# world_clock_2_0.net
KiCad netlist of a schematic drawn in EAGLE
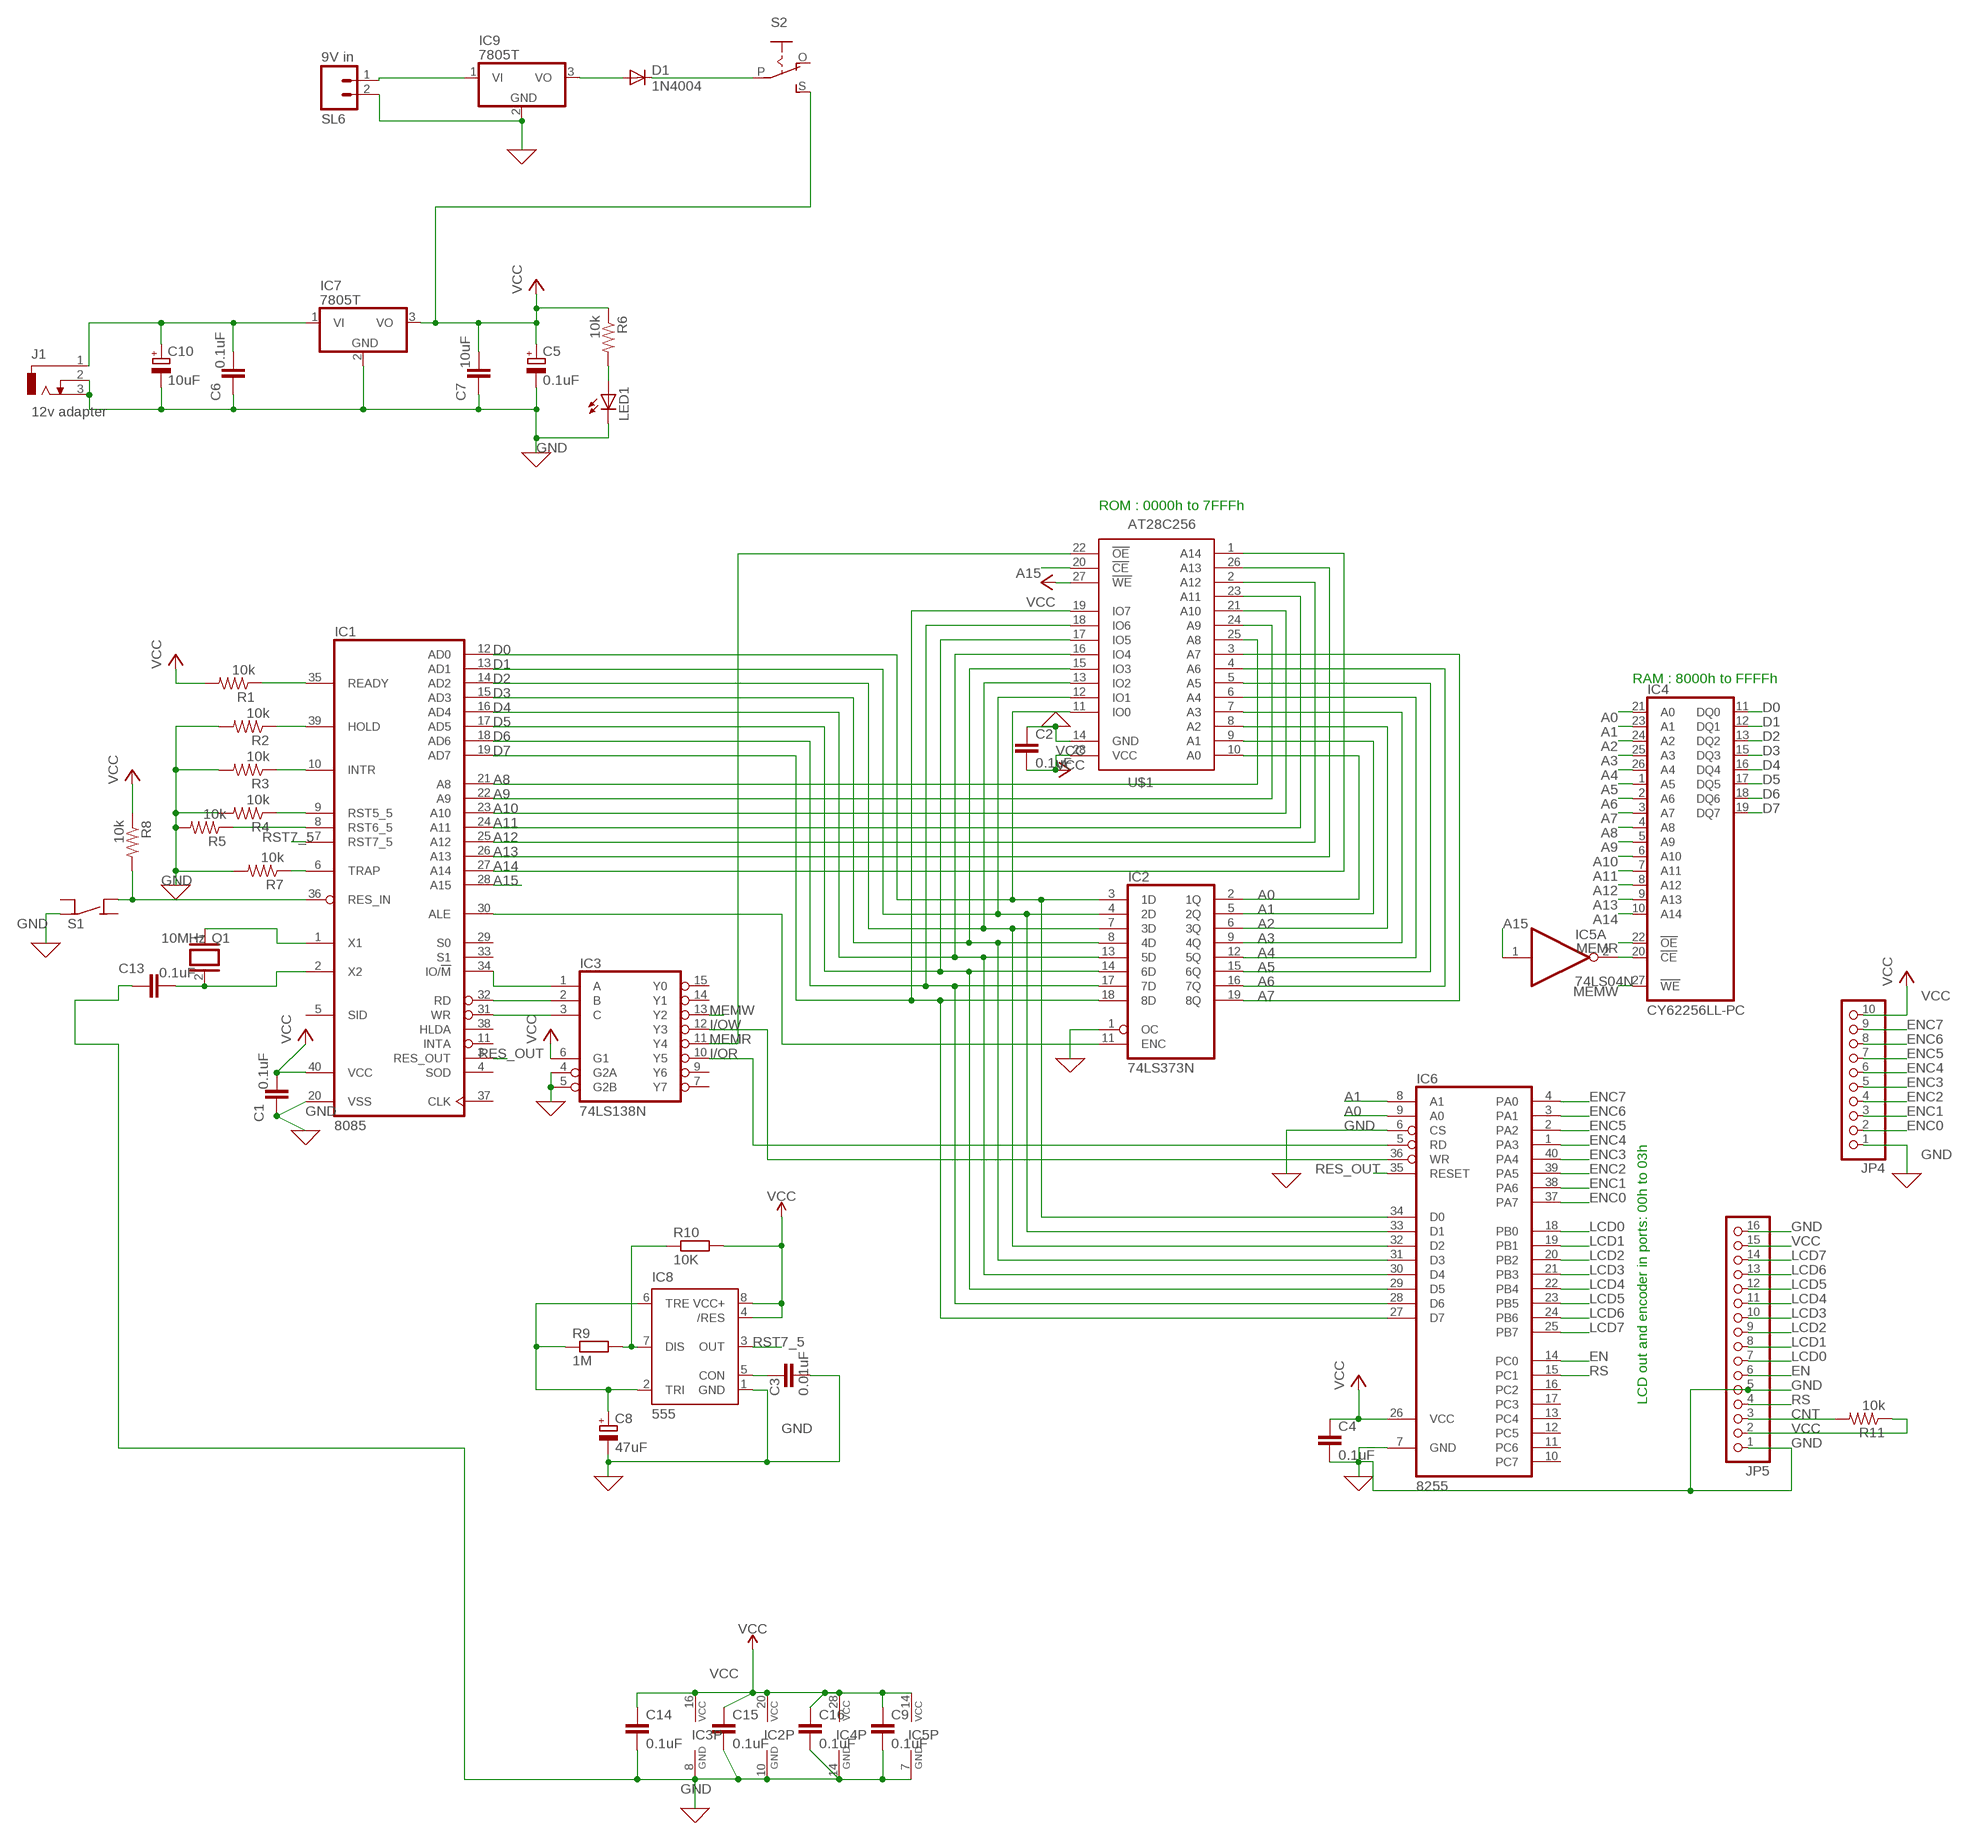
[diagram p0: schematic, sheet 1]

(export (version "E")
  (design (tool "Eeschema 10.0.6"))
  (components
    (comp (ref "C1")
      (value "0.1uF")
      (footprint "eagle-import:C025-024X044")
      (libsource (lib "eagle-import") (part "C-EU025-024X044"))
    )
    (comp (ref "C2")
      (value "0.1uF")
      (footprint "eagle-import:C025-024X044")
      (libsource (lib "eagle-import") (part "C-EU025-024X044"))
    )
    (comp (ref "C3")
      (value "0.01uF")
      (footprint "eagle-import:C2.5-2")
      (libsource (lib "eagle-import") (part "C2.5/2"))
    )
    (comp (ref "C4")
      (value "0.1uF")
      (footprint "eagle-import:C025-024X044")
      (libsource (lib "eagle-import") (part "C-EU025-024X044"))
    )
    (comp (ref "C5")
      (value "0.1uF")
      (footprint "eagle-import:E5-8,5")
      (libsource (lib "eagle-import") (part "CPOL-EUE5-8.5"))
    )
    (comp (ref "C6")
      (value "0.1uF")
      (footprint "eagle-import:C025-024X044")
      (libsource (lib "eagle-import") (part "C-EU025-024X044"))
    )
    (comp (ref "C7")
      (value "10uF")
      (footprint "eagle-import:C025-024X044")
      (libsource (lib "eagle-import") (part "C-EU025-024X044"))
    )
    (comp (ref "C8")
      (value "47uF")
      (footprint "eagle-import:E5-8,5")
      (libsource (lib "eagle-import") (part "CPOL-EUE5-8.5"))
    )
    (comp (ref "C9")
      (value "0.1uF")
      (footprint "eagle-import:C025-024X044")
      (libsource (lib "eagle-import") (part "C-EU025-024X044"))
    )
    (comp (ref "C10")
      (value "10uF")
      (footprint "eagle-import:E5-8,5")
      (libsource (lib "eagle-import") (part "CPOL-EUE5-8.5"))
    )
    (comp (ref "C13")
      (value "0.1uF")
      (footprint "eagle-import:C025-024X044")
      (libsource (lib "eagle-import") (part "C-EU025-024X044"))
    )
    (comp (ref "C14")
      (value "0.1uF")
      (footprint "eagle-import:C025-024X044")
      (libsource (lib "eagle-import") (part "C-EU025-024X044"))
    )
    (comp (ref "C15")
      (value "0.1uF")
      (footprint "eagle-import:C025-024X044")
      (libsource (lib "eagle-import") (part "C-EU025-024X044"))
    )
    (comp (ref "C16")
      (value "0.1uF")
      (footprint "eagle-import:C025-024X044")
      (libsource (lib "eagle-import") (part "C-EU025-024X044"))
    )
    (comp (ref "D1")
      (value "1N4004")
      (footprint "eagle-import:DO41-10")
      (libsource (lib "eagle-import") (part "1N4004"))
    )
    (comp (ref "IC1")
      (value "8085")
      (footprint "eagle-import:DIL40")
      (libsource (lib "eagle-import") (part "8085"))
    )
    (comp (ref "IC2")
      (value "74LS373N")
      (footprint "eagle-import:DIL20")
      (libsource (lib "eagle-import") (part "74373NLS"))
    )
    (comp (ref "IC3")
      (value "74LS138N")
      (footprint "eagle-import:DIL16")
      (libsource (lib "eagle-import") (part "74138NLS"))
    )
    (comp (ref "IC4")
      (value "CY62256LL-PC")
      (footprint "eagle-import:DIL28-6")
      (libsource (lib "eagle-import") (part "CY62256LL-?PC"))
    )
    (comp (ref "IC5")
      (value "74LS04N")
      (footprint "eagle-import:DIL14")
      (libsource (lib "eagle-import") (part "7404NLS"))
    )
    (comp (ref "IC6")
      (value "8255")
      (footprint "eagle-import:DIL40")
      (fields (field (name "MF") "INTERSIL") (field (name "MPN") "IP82C55AZ"))
      (libsource (lib "eagle-import") (part "82C55A"))
    )
    (comp (ref "IC7")
      (value "7805T")
      (footprint "eagle-import:TO220H")
      (libsource (lib "eagle-import") (part "78T05"))
    )
    (comp (ref "IC8")
      (value "555")
      (footprint "eagle-import:DIP08-KIT")
      (libsource (lib "eagle-import") (part "555KIT"))
    )
    (comp (ref "IC9")
      (value "7805T")
      (footprint "eagle-import:TO220H")
      (libsource (lib "eagle-import") (part "78T05"))
    )
    (comp (ref "J1")
      (value "12v adapter")
      (footprint "eagle-import:DCJ0303")
      (libsource (lib "eagle-import") (part "DCJ0303"))
    )
    (comp (ref "JP4")
      (value "PINHD-1X10")
      (footprint "eagle-import:1X10")
      (libsource (lib "eagle-import") (part "PINHD-1X10"))
    )
    (comp (ref "JP5")
      (value "PINHD-1X16")
      (footprint "eagle-import:1X16")
      (libsource (lib "eagle-import") (part "PINHD-1X16"))
    )
    (comp (ref "LED1")
      (value "LED5MM")
      (footprint "eagle-import:LED5MM")
      (libsource (lib "eagle-import") (part "LED5MM"))
    )
    (comp (ref "Q1")
      (value "10MHz")
      (footprint "eagle-import:QS")
      (libsource (lib "eagle-import") (part "XTAL/S"))
    )
    (comp (ref "R1")
      (value "10k")
      (footprint "eagle-import:0207_7")
      (libsource (lib "eagle-import") (part "R-US_0207/7"))
    )
    (comp (ref "R2")
      (value "10k")
      (footprint "eagle-import:0207_7")
      (libsource (lib "eagle-import") (part "R-US_0207/7"))
    )
    (comp (ref "R3")
      (value "10k")
      (footprint "eagle-import:0207_7")
      (libsource (lib "eagle-import") (part "R-US_0207/7"))
    )
    (comp (ref "R4")
      (value "10k")
      (footprint "eagle-import:0207_7")
      (libsource (lib "eagle-import") (part "R-US_0207/7"))
    )
    (comp (ref "R5")
      (value "10k")
      (footprint "eagle-import:0207_7")
      (libsource (lib "eagle-import") (part "R-US_0207/7"))
    )
    (comp (ref "R6")
      (value "10k")
      (footprint "eagle-import:0207_7")
      (libsource (lib "eagle-import") (part "R-US_0207/7"))
    )
    (comp (ref "R7")
      (value "10k")
      (footprint "eagle-import:0207_7")
      (libsource (lib "eagle-import") (part "R-US_0207/7"))
    )
    (comp (ref "R8")
      (value "10k")
      (footprint "eagle-import:0207_7")
      (libsource (lib "eagle-import") (part "R-US_0207/7"))
    )
    (comp (ref "R9")
      (value "1M")
      (footprint "eagle-import:0204_5")
      (libsource (lib "eagle-import") (part "R-EU_0204/5"))
    )
    (comp (ref "R10")
      (value "10K")
      (footprint "eagle-import:0204_5")
      (libsource (lib "eagle-import") (part "R-EU_0204/5"))
    )
    (comp (ref "R11")
      (value "10k")
      (footprint "eagle-import:0207_7")
      (libsource (lib "eagle-import") (part "R-US_0207/7"))
    )
    (comp (ref "S1")
      (value "SPST4B3F-10XX")
      (footprint "eagle-import:B3F-10XX")
      (libsource (lib "eagle-import") (part "SPST4B3F-10XX"))
    )
    (comp (ref "S2")
      (value "EG1218S")
      (footprint "eagle-import:EG1218")
      (libsource (lib "eagle-import") (part "EG1218S"))
    )
    (comp (ref "SL6")
      (value "9V in")
      (footprint "eagle-import:02P")
      (libsource (lib "eagle-import") (part "M02"))
    )
    (comp (ref "U$1")
      (value "AT28C256")
      (footprint "eagle-import:DIL28-6")
      (libsource (lib "eagle-import") (part "AT28C256"))
    )
  )
  (nets
    (net (code "1") (name "/A0") (class "Default")
      (node (ref "IC2") (pin "2") (pinfunction "1Q_2") (pintype "tri_state"))
      (node (ref "IC4") (pin "21") (pinfunction "A0_21") (pintype "input"))
      (node (ref "IC6") (pin "9") (pinfunction "A0_9") (pintype "input"))
      (node (ref "U$1") (pin "10") (pinfunction "A0_10") (pintype "bidirectional"))
    )
    (net (code "2") (name "/A1") (class "Default")
      (node (ref "IC2") (pin "5") (pinfunction "2Q_5") (pintype "tri_state"))
      (node (ref "IC4") (pin "23") (pinfunction "A1_23") (pintype "input"))
      (node (ref "IC6") (pin "8") (pinfunction "A1_8") (pintype "input"))
      (node (ref "U$1") (pin "9") (pinfunction "A1_9") (pintype "bidirectional"))
    )
    (net (code "3") (name "/A2") (class "Default")
      (node (ref "IC2") (pin "6") (pinfunction "3Q_6") (pintype "tri_state"))
      (node (ref "IC4") (pin "24") (pinfunction "A2_24") (pintype "input"))
      (node (ref "U$1") (pin "8") (pinfunction "A2_8") (pintype "bidirectional"))
    )
    (net (code "4") (name "/A3") (class "Default")
      (node (ref "IC2") (pin "9") (pinfunction "4Q_9") (pintype "tri_state"))
      (node (ref "IC4") (pin "25") (pinfunction "A3_25") (pintype "input"))
      (node (ref "U$1") (pin "7") (pinfunction "A3_7") (pintype "bidirectional"))
    )
    (net (code "5") (name "/A4") (class "Default")
      (node (ref "IC2") (pin "12") (pinfunction "5Q_12") (pintype "tri_state"))
      (node (ref "IC4") (pin "26") (pinfunction "A4_26") (pintype "input"))
      (node (ref "U$1") (pin "6") (pinfunction "A4_6") (pintype "bidirectional"))
    )
    (net (code "6") (name "/A5") (class "Default")
      (node (ref "IC2") (pin "15") (pinfunction "6Q_15") (pintype "tri_state"))
      (node (ref "IC4") (pin "1") (pinfunction "A5_1") (pintype "input"))
      (node (ref "U$1") (pin "5") (pinfunction "A5_5") (pintype "bidirectional"))
    )
    (net (code "7") (name "/A6") (class "Default")
      (node (ref "IC2") (pin "16") (pinfunction "7Q_16") (pintype "tri_state"))
      (node (ref "IC4") (pin "2") (pinfunction "A6_2") (pintype "input"))
      (node (ref "U$1") (pin "4") (pinfunction "A6_4") (pintype "bidirectional"))
    )
    (net (code "8") (name "/A7") (class "Default")
      (node (ref "IC2") (pin "19") (pinfunction "8Q_19") (pintype "tri_state"))
      (node (ref "IC4") (pin "3") (pinfunction "A7_3") (pintype "input"))
      (node (ref "U$1") (pin "3") (pinfunction "A7_3") (pintype "bidirectional"))
    )
    (net (code "9") (name "/A8") (class "Default")
      (node (ref "IC1") (pin "21") (pinfunction "A8_21") (pintype "output"))
      (node (ref "IC4") (pin "4") (pinfunction "A8_4") (pintype "input"))
      (node (ref "U$1") (pin "25") (pinfunction "A8_25") (pintype "bidirectional"))
    )
    (net (code "10") (name "/A9") (class "Default")
      (node (ref "IC1") (pin "22") (pinfunction "A9_22") (pintype "output"))
      (node (ref "IC4") (pin "5") (pinfunction "A9_5") (pintype "input"))
      (node (ref "U$1") (pin "24") (pinfunction "A9_24") (pintype "bidirectional"))
    )
    (net (code "11") (name "/A10") (class "Default")
      (node (ref "IC1") (pin "23") (pinfunction "A10_23") (pintype "output"))
      (node (ref "IC4") (pin "6") (pinfunction "A10_6") (pintype "input"))
      (node (ref "U$1") (pin "21") (pinfunction "A10_21") (pintype "bidirectional"))
    )
    (net (code "12") (name "/A11") (class "Default")
      (node (ref "IC1") (pin "24") (pinfunction "A11_24") (pintype "output"))
      (node (ref "IC4") (pin "7") (pinfunction "A11_7") (pintype "input"))
      (node (ref "U$1") (pin "23") (pinfunction "A11_23") (pintype "bidirectional"))
    )
    (net (code "13") (name "/A12") (class "Default")
      (node (ref "IC1") (pin "25") (pinfunction "A12_25") (pintype "output"))
      (node (ref "IC4") (pin "8") (pinfunction "A12_8") (pintype "input"))
      (node (ref "U$1") (pin "2") (pinfunction "A12_2") (pintype "bidirectional"))
    )
    (net (code "14") (name "/A13") (class "Default")
      (node (ref "IC1") (pin "26") (pinfunction "A13_26") (pintype "output"))
      (node (ref "IC4") (pin "9") (pinfunction "A13_9") (pintype "input"))
      (node (ref "U$1") (pin "26") (pinfunction "A13_26") (pintype "bidirectional"))
    )
    (net (code "15") (name "/A14") (class "Default")
      (node (ref "IC1") (pin "27") (pinfunction "A14_27") (pintype "output"))
      (node (ref "IC4") (pin "10") (pinfunction "A14_10") (pintype "input"))
      (node (ref "U$1") (pin "1") (pinfunction "A14_1") (pintype "bidirectional"))
    )
    (net (code "16") (name "/A15") (class "Default")
      (node (ref "IC1") (pin "28") (pinfunction "A15_28") (pintype "output"))
      (node (ref "IC5") (pin "1") (pinfunction "I_1") (pintype "input"))
      (node (ref "U$1") (pin "20") (pinfunction "~{CE}_20") (pintype "bidirectional"))
    )
    (net (code "17") (name "/CNT") (class "Default")
      (node (ref "JP5") (pin "3") (pinfunction "3_3") (pintype "passive"))
      (node (ref "R11") (pin "2") (pinfunction "2_2") (pintype "passive"))
    )
    (net (code "18") (name "/D0") (class "Default")
      (node (ref "IC1") (pin "12") (pinfunction "AD0_12") (pintype "bidirectional"))
      (node (ref "IC2") (pin "3") (pinfunction "1D_3") (pintype "input"))
      (node (ref "IC4") (pin "11") (pinfunction "DQ0_11") (pintype "bidirectional"))
      (node (ref "IC6") (pin "34") (pinfunction "D0_34") (pintype "bidirectional"))
      (node (ref "U$1") (pin "11") (pinfunction "IO0_11") (pintype "bidirectional"))
    )
    (net (code "19") (name "/D1") (class "Default")
      (node (ref "IC1") (pin "13") (pinfunction "AD1_13") (pintype "bidirectional"))
      (node (ref "IC2") (pin "4") (pinfunction "2D_4") (pintype "input"))
      (node (ref "IC4") (pin "12") (pinfunction "DQ1_12") (pintype "bidirectional"))
      (node (ref "IC6") (pin "33") (pinfunction "D1_33") (pintype "bidirectional"))
      (node (ref "U$1") (pin "12") (pinfunction "IO1_12") (pintype "bidirectional"))
    )
    (net (code "20") (name "/D2") (class "Default")
      (node (ref "IC1") (pin "14") (pinfunction "AD2_14") (pintype "bidirectional"))
      (node (ref "IC2") (pin "7") (pinfunction "3D_7") (pintype "input"))
      (node (ref "IC4") (pin "13") (pinfunction "DQ2_13") (pintype "bidirectional"))
      (node (ref "IC6") (pin "32") (pinfunction "D2_32") (pintype "bidirectional"))
      (node (ref "U$1") (pin "13") (pinfunction "IO2_13") (pintype "bidirectional"))
    )
    (net (code "21") (name "/D3") (class "Default")
      (node (ref "IC1") (pin "15") (pinfunction "AD3_15") (pintype "bidirectional"))
      (node (ref "IC2") (pin "8") (pinfunction "4D_8") (pintype "input"))
      (node (ref "IC4") (pin "15") (pinfunction "DQ3_15") (pintype "bidirectional"))
      (node (ref "IC6") (pin "31") (pinfunction "D3_31") (pintype "bidirectional"))
      (node (ref "U$1") (pin "15") (pinfunction "IO3_15") (pintype "bidirectional"))
    )
    (net (code "22") (name "/D4") (class "Default")
      (node (ref "IC1") (pin "16") (pinfunction "AD4_16") (pintype "bidirectional"))
      (node (ref "IC2") (pin "13") (pinfunction "5D_13") (pintype "input"))
      (node (ref "IC4") (pin "16") (pinfunction "DQ4_16") (pintype "bidirectional"))
      (node (ref "IC6") (pin "30") (pinfunction "D4_30") (pintype "bidirectional"))
      (node (ref "U$1") (pin "16") (pinfunction "IO4_16") (pintype "bidirectional"))
    )
    (net (code "23") (name "/D5") (class "Default")
      (node (ref "IC1") (pin "17") (pinfunction "AD5_17") (pintype "bidirectional"))
      (node (ref "IC2") (pin "14") (pinfunction "6D_14") (pintype "input"))
      (node (ref "IC4") (pin "17") (pinfunction "DQ5_17") (pintype "bidirectional"))
      (node (ref "IC6") (pin "29") (pinfunction "D5_29") (pintype "bidirectional"))
      (node (ref "U$1") (pin "17") (pinfunction "IO5_17") (pintype "bidirectional"))
    )
    (net (code "24") (name "/D6") (class "Default")
      (node (ref "IC1") (pin "18") (pinfunction "AD6_18") (pintype "bidirectional"))
      (node (ref "IC2") (pin "17") (pinfunction "7D_17") (pintype "input"))
      (node (ref "IC4") (pin "18") (pinfunction "DQ6_18") (pintype "bidirectional"))
      (node (ref "IC6") (pin "28") (pinfunction "D6_28") (pintype "bidirectional"))
      (node (ref "U$1") (pin "18") (pinfunction "IO6_18") (pintype "bidirectional"))
    )
    (net (code "25") (name "/D7") (class "Default")
      (node (ref "IC1") (pin "19") (pinfunction "AD7_19") (pintype "bidirectional"))
      (node (ref "IC2") (pin "18") (pinfunction "8D_18") (pintype "input"))
      (node (ref "IC4") (pin "19") (pinfunction "DQ7_19") (pintype "bidirectional"))
      (node (ref "IC6") (pin "27") (pinfunction "D7_27") (pintype "bidirectional"))
      (node (ref "U$1") (pin "19") (pinfunction "IO7_19") (pintype "bidirectional"))
    )
    (net (code "26") (name "/EN") (class "Default")
      (node (ref "IC6") (pin "14") (pinfunction "PC0_14") (pintype "bidirectional"))
      (node (ref "JP5") (pin "6") (pinfunction "6_6") (pintype "passive"))
    )
    (net (code "27") (name "/ENC0") (class "Default")
      (node (ref "IC6") (pin "37") (pinfunction "PA7_37") (pintype "bidirectional"))
      (node (ref "JP4") (pin "2") (pinfunction "2_2") (pintype "passive"))
    )
    (net (code "28") (name "/ENC1") (class "Default")
      (node (ref "IC6") (pin "38") (pinfunction "PA6_38") (pintype "bidirectional"))
      (node (ref "JP4") (pin "3") (pinfunction "3_3") (pintype "passive"))
    )
    (net (code "29") (name "/ENC2") (class "Default")
      (node (ref "IC6") (pin "39") (pinfunction "PA5_39") (pintype "bidirectional"))
      (node (ref "JP4") (pin "4") (pinfunction "4_4") (pintype "passive"))
    )
    (net (code "30") (name "/ENC3") (class "Default")
      (node (ref "IC6") (pin "40") (pinfunction "PA4_40") (pintype "bidirectional"))
      (node (ref "JP4") (pin "5") (pinfunction "5_5") (pintype "passive"))
    )
    (net (code "31") (name "/ENC4") (class "Default")
      (node (ref "IC6") (pin "1") (pinfunction "PA3_1") (pintype "bidirectional"))
      (node (ref "JP4") (pin "6") (pinfunction "6_6") (pintype "passive"))
    )
    (net (code "32") (name "/ENC5") (class "Default")
      (node (ref "IC6") (pin "2") (pinfunction "PA2_2") (pintype "bidirectional"))
      (node (ref "JP4") (pin "7") (pinfunction "7_7") (pintype "passive"))
    )
    (net (code "33") (name "/ENC6") (class "Default")
      (node (ref "IC6") (pin "3") (pinfunction "PA1_3") (pintype "bidirectional"))
      (node (ref "JP4") (pin "8") (pinfunction "8_8") (pintype "passive"))
    )
    (net (code "34") (name "/ENC7") (class "Default")
      (node (ref "IC6") (pin "4") (pinfunction "PA0_4") (pintype "bidirectional"))
      (node (ref "JP4") (pin "9") (pinfunction "9_9") (pintype "passive"))
    )
    (net (code "35") (name "/I{slash}OR") (class "Default")
      (node (ref "IC3") (pin "10") (pinfunction "Y5_10") (pintype "output"))
      (node (ref "IC6") (pin "5") (pinfunction "RD_5") (pintype "input"))
    )
    (net (code "36") (name "/I{slash}OW") (class "Default")
      (node (ref "IC3") (pin "12") (pinfunction "Y3_12") (pintype "output"))
      (node (ref "IC6") (pin "36") (pinfunction "WR_36") (pintype "input"))
    )
    (net (code "37") (name "/LCD0") (class "Default")
      (node (ref "IC6") (pin "18") (pinfunction "PB0_18") (pintype "bidirectional"))
      (node (ref "JP5") (pin "7") (pinfunction "7_7") (pintype "passive"))
    )
    (net (code "38") (name "/LCD1") (class "Default")
      (node (ref "IC6") (pin "19") (pinfunction "PB1_19") (pintype "bidirectional"))
      (node (ref "JP5") (pin "8") (pinfunction "8_8") (pintype "passive"))
    )
    (net (code "39") (name "/LCD2") (class "Default")
      (node (ref "IC6") (pin "20") (pinfunction "PB2_20") (pintype "bidirectional"))
      (node (ref "JP5") (pin "9") (pinfunction "9_9") (pintype "passive"))
    )
    (net (code "40") (name "/LCD3") (class "Default")
      (node (ref "IC6") (pin "21") (pinfunction "PB3_21") (pintype "bidirectional"))
      (node (ref "JP5") (pin "10") (pinfunction "10_10") (pintype "passive"))
    )
    (net (code "41") (name "/LCD4") (class "Default")
      (node (ref "IC6") (pin "22") (pinfunction "PB4_22") (pintype "bidirectional"))
      (node (ref "JP5") (pin "11") (pinfunction "11_11") (pintype "passive"))
    )
    (net (code "42") (name "/LCD5") (class "Default")
      (node (ref "IC6") (pin "23") (pinfunction "PB5_23") (pintype "bidirectional"))
      (node (ref "JP5") (pin "12") (pinfunction "12_12") (pintype "passive"))
    )
    (net (code "43") (name "/LCD6") (class "Default")
      (node (ref "IC6") (pin "24") (pinfunction "PB6_24") (pintype "bidirectional"))
      (node (ref "JP5") (pin "13") (pinfunction "13_13") (pintype "passive"))
    )
    (net (code "44") (name "/LCD7") (class "Default")
      (node (ref "IC6") (pin "25") (pinfunction "PB7_25") (pintype "bidirectional"))
      (node (ref "JP5") (pin "14") (pinfunction "14_14") (pintype "passive"))
    )
    (net (code "45") (name "/MEMR") (class "Default")
      (node (ref "IC3") (pin "11") (pinfunction "Y4_11") (pintype "output"))
      (node (ref "IC4") (pin "22") (pinfunction "~{OE}_22") (pintype "input"))
      (node (ref "U$1") (pin "22") (pinfunction "~{OE}_22") (pintype "bidirectional"))
    )
    (net (code "46") (name "/MEMW") (class "Default")
      (node (ref "IC3") (pin "13") (pinfunction "Y2_13") (pintype "output"))
      (node (ref "IC4") (pin "27") (pinfunction "~{WE}_27") (pintype "input"))
    )
    (net (code "47") (name "/RES_OUT") (class "Default")
      (node (ref "IC1") (pin "3") (pinfunction "RES_OUT_3") (pintype "output"))
      (node (ref "IC6") (pin "35") (pinfunction "RESET_35") (pintype "input"))
    )
    (net (code "48") (name "/RS") (class "Default")
      (node (ref "IC6") (pin "15") (pinfunction "PC1_15") (pintype "bidirectional"))
      (node (ref "JP5") (pin "4") (pinfunction "4_4") (pintype "passive"))
    )
    (net (code "49") (name "/RST7_5") (class "Default")
      (node (ref "IC1") (pin "7") (pinfunction "RST7_5_7") (pintype "input"))
      (node (ref "IC8") (pin "3") (pinfunction "OUT_3") (pintype "output"))
    )
    (net (code "50") (name "GND") (class "Default")
      (node (ref "C1") (pin "1") (pinfunction "1_1") (pintype "passive"))
      (node (ref "C10") (pin "-") (pinfunction "-_-") (pintype "passive"))
      (node (ref "C13") (pin "1") (pinfunction "1_1") (pintype "passive"))
      (node (ref "C14") (pin "2") (pinfunction "2_2") (pintype "passive"))
      (node (ref "C15") (pin "2") (pinfunction "2_2") (pintype "passive"))
      (node (ref "C16") (pin "2") (pinfunction "2_2") (pintype "passive"))
      (node (ref "C2") (pin "1") (pinfunction "1_1") (pintype "passive"))
      (node (ref "C3") (pin "2") (pinfunction "2_2") (pintype "passive"))
      (node (ref "C4") (pin "2") (pinfunction "2_2") (pintype "passive"))
      (node (ref "C5") (pin "-") (pinfunction "-_-") (pintype "passive"))
      (node (ref "C6") (pin "1") (pinfunction "1_1") (pintype "passive"))
      (node (ref "C7") (pin "1") (pinfunction "1_1") (pintype "passive"))
      (node (ref "C8") (pin "-") (pinfunction "-_-") (pintype "passive"))
      (node (ref "C9") (pin "2") (pinfunction "2_2") (pintype "passive"))
      (node (ref "IC1") (pin "20") (pinfunction "VSS_20") (pintype "power_in"))
      (node (ref "IC2") (pin "1") (pinfunction "OC_1") (pintype "input"))
      (node (ref "IC2") (pin "10") (pinfunction "GND_10") (pintype "power_in"))
      (node (ref "IC3") (pin "4") (pinfunction "G2A_4") (pintype "input"))
      (node (ref "IC3") (pin "5") (pinfunction "G2B_5") (pintype "input"))
      (node (ref "IC3") (pin "8") (pinfunction "GND_8") (pintype "power_in"))
      (node (ref "IC4") (pin "14") (pinfunction "GND_14") (pintype "power_in"))
      (node (ref "IC5") (pin "7") (pinfunction "GND_7") (pintype "power_in"))
      (node (ref "IC6") (pin "6") (pinfunction "CS_6") (pintype "input"))
      (node (ref "IC6") (pin "7") (pinfunction "GND_7") (pintype "power_in"))
      (node (ref "IC7") (pin "2") (pinfunction "GND_2") (pintype "passive"))
      (node (ref "IC8") (pin "1") (pinfunction "GND_1") (pintype "power_in"))
      (node (ref "IC9") (pin "2") (pinfunction "GND_2") (pintype "passive"))
      (node (ref "J1") (pin "2") (pinfunction "2_2") (pintype "passive"))
      (node (ref "J1") (pin "3") (pinfunction "3_3") (pintype "passive"))
      (node (ref "JP4") (pin "1") (pinfunction "1_1") (pintype "passive"))
      (node (ref "JP5") (pin "1") (pinfunction "1_1") (pintype "passive"))
      (node (ref "JP5") (pin "16") (pinfunction "16_16") (pintype "passive"))
      (node (ref "JP5") (pin "5") (pinfunction "5_5") (pintype "passive"))
      (node (ref "LED1") (pin "K") (pinfunction "C_K") (pintype "passive"))
      (node (ref "R2") (pin "2") (pinfunction "2_2") (pintype "passive"))
      (node (ref "R3") (pin "2") (pinfunction "2_2") (pintype "passive"))
      (node (ref "R4") (pin "2") (pinfunction "2_2") (pintype "passive"))
      (node (ref "R5") (pin "2") (pinfunction "2_2") (pintype "passive"))
      (node (ref "R7") (pin "2") (pinfunction "2_2") (pintype "passive"))
      (node (ref "S1") (pin "COM@1") (pinfunction "COM_COM@1") (pintype "passive"))
      (node (ref "SL6") (pin "2") (pinfunction "2_2") (pintype "passive"))
      (node (ref "U$1") (pin "14") (pinfunction "GND_14") (pintype "bidirectional"))
    )
    (net (code "51") (name "Net-(D1-PadC)") (class "Default")
      (node (ref "D1") (pin "C") (pinfunction "C_C") (pintype "passive"))
      (node (ref "S2") (pin "P") (pinfunction "P_P") (pintype "passive"))
    )
    (net (code "52") (name "Net-(IC1-ALE)") (class "Default")
      (node (ref "IC1") (pin "30") (pinfunction "ALE_30") (pintype "output"))
      (node (ref "IC2") (pin "11") (pinfunction "ENC_11") (pintype "input"))
    )
    (net (code "53") (name "Net-(IC1-HOLD)") (class "Default")
      (node (ref "IC1") (pin "39") (pinfunction "HOLD_39") (pintype "input"))
      (node (ref "R2") (pin "1") (pinfunction "1_1") (pintype "passive"))
    )
    (net (code "54") (name "Net-(IC1-INTR)") (class "Default")
      (node (ref "IC1") (pin "10") (pinfunction "INTR_10") (pintype "input"))
      (node (ref "R3") (pin "1") (pinfunction "1_1") (pintype "passive"))
    )
    (net (code "55") (name "Net-(IC1-IO{slash}~{M})") (class "Default")
      (node (ref "IC1") (pin "34") (pinfunction "IO/~{M}_34") (pintype "output"))
      (node (ref "IC3") (pin "1") (pinfunction "A_1") (pintype "input"))
    )
    (net (code "56") (name "Net-(IC1-RD)") (class "Default")
      (node (ref "IC1") (pin "32") (pinfunction "RD_32") (pintype "output"))
      (node (ref "IC3") (pin "2") (pinfunction "B_2") (pintype "input"))
    )
    (net (code "57") (name "Net-(IC1-READY)") (class "Default")
      (node (ref "IC1") (pin "35") (pinfunction "READY_35") (pintype "input"))
      (node (ref "R1") (pin "1") (pinfunction "1_1") (pintype "passive"))
    )
    (net (code "58") (name "Net-(IC1-RES_IN)") (class "Default")
      (node (ref "IC1") (pin "36") (pinfunction "RES_IN_36") (pintype "input"))
      (node (ref "R8") (pin "2") (pinfunction "2_2") (pintype "passive"))
      (node (ref "S1") (pin "NO@2") (pinfunction "NO_NO@2") (pintype "passive"))
    )
    (net (code "59") (name "Net-(IC1-RST5_5)") (class "Default")
      (node (ref "IC1") (pin "9") (pinfunction "RST5_5_9") (pintype "input"))
      (node (ref "R4") (pin "1") (pinfunction "1_1") (pintype "passive"))
    )
    (net (code "60") (name "Net-(IC1-RST6_5)") (class "Default")
      (node (ref "IC1") (pin "8") (pinfunction "RST6_5_8") (pintype "input"))
      (node (ref "R5") (pin "1") (pinfunction "1_1") (pintype "passive"))
    )
    (net (code "61") (name "Net-(IC1-TRAP)") (class "Default")
      (node (ref "IC1") (pin "6") (pinfunction "TRAP_6") (pintype "input"))
      (node (ref "R7") (pin "1") (pinfunction "1_1") (pintype "passive"))
    )
    (net (code "62") (name "Net-(IC1-WR)") (class "Default")
      (node (ref "IC1") (pin "31") (pinfunction "WR_31") (pintype "output"))
      (node (ref "IC3") (pin "3") (pinfunction "C_3") (pintype "input"))
    )
    (net (code "63") (name "Net-(IC1-X1)") (class "Default")
      (node (ref "IC1") (pin "1") (pinfunction "X1_1") (pintype "input"))
      (node (ref "Q1") (pin "1") (pinfunction "1_1") (pintype "passive"))
    )
    (net (code "64") (name "Net-(IC1-X2)") (class "Default")
      (node (ref "C13") (pin "2") (pinfunction "2_2") (pintype "passive"))
      (node (ref "IC1") (pin "2") (pinfunction "X2_2") (pintype "input"))
      (node (ref "Q1") (pin "2") (pinfunction "2_2") (pintype "passive"))
    )
    (net (code "65") (name "Net-(IC4A-~{CE})") (class "Default")
      (node (ref "IC4") (pin "20") (pinfunction "~{CE}_20") (pintype "input"))
      (node (ref "IC5") (pin "2") (pinfunction "O_2") (pintype "output"))
    )
    (net (code "66") (name "Net-(IC7-VI)") (class "Default")
      (node (ref "C10") (pin "+") (pinfunction "+_+") (pintype "passive"))
      (node (ref "C6") (pin "2") (pinfunction "2_2") (pintype "passive"))
      (node (ref "IC7") (pin "1") (pinfunction "VI_1") (pintype "input"))
      (node (ref "J1") (pin "1") (pinfunction "1_1") (pintype "passive"))
    )
    (net (code "67") (name "Net-(IC8-CON)") (class "Default")
      (node (ref "C3") (pin "1") (pinfunction "1_1") (pintype "passive"))
      (node (ref "IC8") (pin "5") (pinfunction "CON_5") (pintype "input"))
    )
    (net (code "68") (name "Net-(IC8-DIS)") (class "Default")
      (node (ref "IC8") (pin "7") (pinfunction "DIS_7") (pintype "input"))
      (node (ref "R10") (pin "1") (pinfunction "1_1") (pintype "passive"))
      (node (ref "R9") (pin "2") (pinfunction "2_2") (pintype "passive"))
    )
    (net (code "69") (name "Net-(IC8-TRE)") (class "Default")
      (node (ref "C8") (pin "+") (pinfunction "+_+") (pintype "passive"))
      (node (ref "IC8") (pin "2") (pinfunction "TRI_2") (pintype "input"))
      (node (ref "IC8") (pin "6") (pinfunction "TRE_6") (pintype "input"))
      (node (ref "R9") (pin "1") (pinfunction "1_1") (pintype "passive"))
    )
    (net (code "70") (name "Net-(IC9-VI)") (class "Default")
      (node (ref "IC9") (pin "1") (pinfunction "VI_1") (pintype "input"))
      (node (ref "SL6") (pin "1") (pinfunction "1_1") (pintype "passive"))
    )
    (net (code "71") (name "Net-(IC9-VO)") (class "Default")
      (node (ref "D1") (pin "A") (pinfunction "A_A") (pintype "passive"))
      (node (ref "IC9") (pin "3") (pinfunction "VO_3") (pintype "passive"))
    )
    (net (code "72") (name "Net-(LED1-PadA)") (class "Default")
      (node (ref "LED1") (pin "A") (pinfunction "A_A") (pintype "passive"))
      (node (ref "R6") (pin "2") (pinfunction "2_2") (pintype "passive"))
    )
    (net (code "73") (name "VCC") (class "Default")
      (node (ref "C1") (pin "2") (pinfunction "2_2") (pintype "passive"))
      (node (ref "C14") (pin "1") (pinfunction "1_1") (pintype "passive"))
      (node (ref "C15") (pin "1") (pinfunction "1_1") (pintype "passive"))
      (node (ref "C16") (pin "1") (pinfunction "1_1") (pintype "passive"))
      (node (ref "C2") (pin "2") (pinfunction "2_2") (pintype "passive"))
      (node (ref "C4") (pin "1") (pinfunction "1_1") (pintype "passive"))
      (node (ref "C5") (pin "+") (pinfunction "+_+") (pintype "passive"))
      (node (ref "C7") (pin "2") (pinfunction "2_2") (pintype "passive"))
      (node (ref "C9") (pin "1") (pinfunction "1_1") (pintype "passive"))
      (node (ref "IC1") (pin "40") (pinfunction "VCC_40") (pintype "power_in"))
      (node (ref "IC2") (pin "20") (pinfunction "VCC_20") (pintype "power_in"))
      (node (ref "IC3") (pin "16") (pinfunction "VCC_16") (pintype "power_in"))
      (node (ref "IC3") (pin "6") (pinfunction "G1_6") (pintype "input"))
      (node (ref "IC4") (pin "28") (pinfunction "VCC_28") (pintype "power_in"))
      (node (ref "IC5") (pin "14") (pinfunction "VCC_14") (pintype "power_in"))
      (node (ref "IC6") (pin "26") (pinfunction "VCC_26") (pintype "power_in"))
      (node (ref "IC7") (pin "3") (pinfunction "VO_3") (pintype "passive"))
      (node (ref "IC8") (pin "4") (pinfunction "/RES_4") (pintype "input"))
      (node (ref "IC8") (pin "8") (pinfunction "VCC+_8") (pintype "power_in"))
      (node (ref "JP4") (pin "10") (pinfunction "10_10") (pintype "passive"))
      (node (ref "JP5") (pin "15") (pinfunction "15_15") (pintype "passive"))
      (node (ref "JP5") (pin "2") (pinfunction "2_2") (pintype "passive"))
      (node (ref "R1") (pin "2") (pinfunction "2_2") (pintype "passive"))
      (node (ref "R10") (pin "2") (pinfunction "2_2") (pintype "passive"))
      (node (ref "R11") (pin "1") (pinfunction "1_1") (pintype "passive"))
      (node (ref "R6") (pin "1") (pinfunction "1_1") (pintype "passive"))
      (node (ref "R8") (pin "1") (pinfunction "1_1") (pintype "passive"))
      (node (ref "S2") (pin "S") (pinfunction "S_S") (pintype "passive"))
      (node (ref "U$1") (pin "27") (pinfunction "~{WE}_27") (pintype "bidirectional"))
      (node (ref "U$1") (pin "28") (pinfunction "VCC_28") (pintype "bidirectional"))
    )
    (net (code "74") (name "unconnected-(IC1-CLK-Pad37)") (class "Default")
      (node (ref "IC1") (pin "37") (pinfunction "CLK_37") (pintype "output"))
    )
    (net (code "75") (name "unconnected-(IC1-HLDA-Pad38)") (class "Default")
      (node (ref "IC1") (pin "38") (pinfunction "HLDA_38") (pintype "output"))
    )
    (net (code "76") (name "unconnected-(IC1-INTA-Pad11)") (class "Default")
      (node (ref "IC1") (pin "11") (pinfunction "INTA_11") (pintype "output"))
    )
    (net (code "77") (name "unconnected-(IC1-S0-Pad29)") (class "Default")
      (node (ref "IC1") (pin "29") (pinfunction "S0_29") (pintype "output"))
    )
    (net (code "78") (name "unconnected-(IC1-S1-Pad33)") (class "Default")
      (node (ref "IC1") (pin "33") (pinfunction "S1_33") (pintype "output"))
    )
    (net (code "79") (name "unconnected-(IC1-SID-Pad5)") (class "Default")
      (node (ref "IC1") (pin "5") (pinfunction "SID_5") (pintype "input"))
    )
    (net (code "80") (name "unconnected-(IC1-SOD-Pad4)") (class "Default")
      (node (ref "IC1") (pin "4") (pinfunction "SOD_4") (pintype "output"))
    )
    (net (code "81") (name "unconnected-(IC3A-Y0-Pad15)") (class "Default")
      (node (ref "IC3") (pin "15") (pinfunction "Y0_15") (pintype "output"))
    )
    (net (code "82") (name "unconnected-(IC3A-Y1-Pad14)") (class "Default")
      (node (ref "IC3") (pin "14") (pinfunction "Y1_14") (pintype "output"))
    )
    (net (code "83") (name "unconnected-(IC3A-Y6-Pad9)") (class "Default")
      (node (ref "IC3") (pin "9") (pinfunction "Y6_9") (pintype "output"))
    )
    (net (code "84") (name "unconnected-(IC3A-Y7-Pad7)") (class "Default")
      (node (ref "IC3") (pin "7") (pinfunction "Y7_7") (pintype "output"))
    )
    (net (code "85") (name "unconnected-(IC6-PC2-Pad16)") (class "Default")
      (node (ref "IC6") (pin "16") (pinfunction "PC2_16") (pintype "bidirectional"))
    )
    (net (code "86") (name "unconnected-(IC6-PC3-Pad17)") (class "Default")
      (node (ref "IC6") (pin "17") (pinfunction "PC3_17") (pintype "bidirectional"))
    )
    (net (code "87") (name "unconnected-(IC6-PC4-Pad13)") (class "Default")
      (node (ref "IC6") (pin "13") (pinfunction "PC4_13") (pintype "bidirectional"))
    )
    (net (code "88") (name "unconnected-(IC6-PC5-Pad12)") (class "Default")
      (node (ref "IC6") (pin "12") (pinfunction "PC5_12") (pintype "bidirectional"))
    )
    (net (code "89") (name "unconnected-(IC6-PC6-Pad11)") (class "Default")
      (node (ref "IC6") (pin "11") (pinfunction "PC6_11") (pintype "bidirectional"))
    )
    (net (code "90") (name "unconnected-(IC6-PC7-Pad10)") (class "Default")
      (node (ref "IC6") (pin "10") (pinfunction "PC7_10") (pintype "bidirectional"))
    )
    (net (code "91") (name "unconnected-(S1-COM-PadCOM@2)") (class "Default")
      (node (ref "S1") (pin "COM@2") (pinfunction "COM_COM@2") (pintype "passive"))
    )
    (net (code "92") (name "unconnected-(S1-NO-PadNO@1)") (class "Default")
      (node (ref "S1") (pin "NO@1") (pinfunction "NO_NO@1") (pintype "passive"))
    )
    (net (code "93") (name "unconnected-(S2-PadO)") (class "Default")
      (node (ref "S2") (pin "O") (pinfunction "O_O") (pintype "passive"))
    )
  )
)
